# Zasilanie.net
KiCad netlist of a schematic drawn in Altium Designer
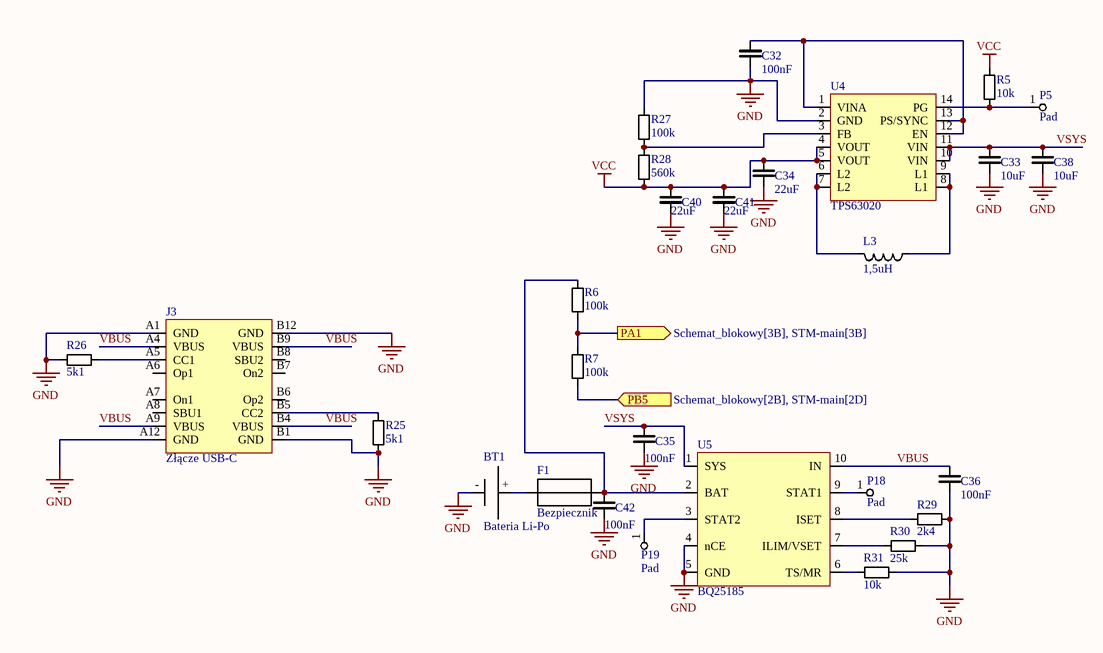
[diagram p0: Zasilanie.SchDoc]

(export (version "E")
  (design (tool "Eeschema 10.0.6"))
  (components
    (comp (ref "BT1")
      (value "Bateria Li-Po")
      (footprint "LP623255 3,7V 1100mAh")
      (fields (field (name "PARTNUMBER") "LP623255 3,7V 1100mAh"))
      (libsource (lib "Zasilanie") (part "Bateria Li-Po"))
    )
    (comp (ref "C32")
      (value "100nF")
      (footprint "0603_CAP")
      (description "Ceramic capacitor")
      (libsource (lib "Cap") (part "Cap"))
    )
    (comp (ref "C33")
      (value "10uF")
      (footprint "0603_CAP")
      (description "Ceramic capacitor")
      (libsource (lib "Cap") (part "Cap"))
    )
    (comp (ref "C34")
      (value "22uF")
      (footprint "0603_CAP")
      (description "Ceramic capacitor")
      (libsource (lib "Cap") (part "Cap"))
    )
    (comp (ref "C35")
      (value "100nF")
      (footprint "0603_CAP")
      (description "Ceramic capacitor")
      (libsource (lib "Cap") (part "Cap"))
    )
    (comp (ref "C36")
      (value "100nF")
      (footprint "0603_CAP")
      (description "Ceramic capacitor")
      (libsource (lib "Cap") (part "Cap"))
    )
    (comp (ref "C38")
      (value "10uF")
      (footprint "0603_CAP")
      (description "Ceramic capacitor")
      (libsource (lib "Cap") (part "Cap"))
    )
    (comp (ref "C40")
      (value "22uF")
      (footprint "0603_CAP")
      (description "Ceramic capacitor")
      (libsource (lib "Cap") (part "Cap"))
    )
    (comp (ref "C41")
      (value "22uF")
      (footprint "0603_CAP")
      (description "Ceramic capacitor")
      (libsource (lib "Cap") (part "Cap"))
    )
    (comp (ref "C42")
      (value "100nF")
      (footprint "0603_CAP")
      (description "Ceramic capacitor")
      (libsource (lib "Cap") (part "Cap"))
    )
    (comp (ref "F1")
      (value "Bezpiecznik")
      (footprint "0603_FUSE")
      (fields (field (name "PARTNUMBER") "FMC16132WBTP"))
      (libsource (lib "Zasilanie") (part "Bezpiecznik"))
    )
    (comp (ref "J3")
      (value "Złącze USB-C")
      (footprint "HRO_TYPE-C-31-M-12")
      (fields (field (name "PARTNUMBER") "1332645"))
      (libsource (lib "Zasilanie") (part "Zlacze USB-C"))
    )
    (comp (ref "L3")
      (value "1,5uH")
      (footprint "0603_IND")
      (description "Inductor")
      (fields (field (name "PARTNUMBER") "LSCNB1608HKT1R5MD"))
      (libsource (lib "Inductor") (part "Inductor"))
    )
    (comp (ref "P5") (value "Pad") (footprint "pad") (libsource (lib "PinLutowniczy") (part "Pad")))
    (comp (ref "P18") (value "Pad") (footprint "pad") (libsource (lib "PinLutowniczy") (part "Pad")))
    (comp (ref "P19") (value "Pad") (footprint "pad") (libsource (lib "PinLutowniczy") (part "Pad")))
    (comp (ref "R5")
      (value "10k")
      (footprint "0603_RES")
      (description "Resistor")
      (libsource (lib "RES") (part "RES"))
    )
    (comp (ref "R6")
      (value "100k")
      (footprint "0603_RES")
      (description "Resistor")
      (libsource (lib "RES") (part "RES"))
    )
    (comp (ref "R7")
      (value "100k")
      (footprint "0603_RES")
      (description "Resistor")
      (libsource (lib "RES") (part "RES"))
    )
    (comp (ref "R25")
      (value "5k1")
      (footprint "0603_RES")
      (description "Resistor")
      (libsource (lib "RES") (part "RES"))
    )
    (comp (ref "R26")
      (value "5k1")
      (footprint "0603_RES")
      (description "Resistor")
      (libsource (lib "RES") (part "RES"))
    )
    (comp (ref "R27")
      (value "100k")
      (footprint "0603_RES")
      (description "Resistor")
      (libsource (lib "RES") (part "RES"))
    )
    (comp (ref "R28")
      (value "560k")
      (footprint "0603_RES")
      (description "Resistor")
      (libsource (lib "RES") (part "RES"))
    )
    (comp (ref "R29")
      (value "2k4")
      (footprint "0603_RES")
      (description "Resistor")
      (libsource (lib "RES") (part "RES"))
    )
    (comp (ref "R30")
      (value "25k")
      (footprint "0603_RES")
      (description "Resistor")
      (libsource (lib "RES") (part "RES"))
    )
    (comp (ref "R31")
      (value "10k")
      (footprint "0603_RES")
      (description "Resistor")
      (libsource (lib "RES") (part "RES"))
    )
    (comp (ref "U4")
      (value "TPS63020")
      (footprint "IC_TPS63020DSJT")
      (description "Przetwornica impulsowa")
      (fields (field (name "PARTNUMBER") "TPS63020DSJR"))
      (libsource (lib "Zasilanie") (part "Stabilizator napięcia"))
    )
    (comp (ref "U5")
      (value "BQ25185")
      (footprint "SON50P250X250X80-11N")
      (description "Battery charger")
      (fields (field (name "PARTNUMBER") "BQ25185DLHR"))
      (libsource (lib "Zasilanie") (part "BQ25185"))
    )
  )
  (nets
    (net (code "1") (name "/PA1") (class "Default")
      (node (ref "R6") (pin "1") (pinfunction "1_1") (pintype "passive"))
      (node (ref "R7") (pin "2") (pinfunction "2_2") (pintype "passive"))
    )
    (net (code "2") (name "/PB5") (class "Default")
      (node (ref "R7") (pin "1") (pinfunction "1_1") (pintype "passive"))
    )
    (net (code "3") (name "/VBUS") (class "Default")
      (node (ref "C36") (pin "2") (pinfunction "2_2") (pintype "passive"))
      (node (ref "J3") (pin "A4") (pinfunction "VBUS_A4") (pintype "passive"))
      (node (ref "J3") (pin "A9") (pinfunction "VBUS_A9") (pintype "passive"))
      (node (ref "J3") (pin "B4") (pinfunction "VBUS_B4") (pintype "passive"))
      (node (ref "J3") (pin "B9") (pinfunction "VBUS_B9") (pintype "passive"))
      (node (ref "U5") (pin "10") (pinfunction "IN_10") (pintype "passive"))
    )
    (net (code "4") (name "/VSYS") (class "Default")
      (node (ref "C33") (pin "2") (pinfunction "2_2") (pintype "passive"))
      (node (ref "C35") (pin "2") (pinfunction "2_2") (pintype "passive"))
      (node (ref "C38") (pin "2") (pinfunction "2_2") (pintype "passive"))
      (node (ref "U4") (pin "10") (pinfunction "VIN_10") (pintype "passive"))
      (node (ref "U4") (pin "11") (pinfunction "VIN_11") (pintype "passive"))
      (node (ref "U5") (pin "1") (pinfunction "SYS_1") (pintype "passive"))
    )
    (net (code "5") (name "GND") (class "Default")
      (node (ref "BT1") (pin "-") (pintype "passive"))
      (node (ref "C32") (pin "1") (pinfunction "1_1") (pintype "passive"))
      (node (ref "C33") (pin "1") (pinfunction "1_1") (pintype "passive"))
      (node (ref "C34") (pin "1") (pinfunction "1_1") (pintype "passive"))
      (node (ref "C35") (pin "1") (pinfunction "1_1") (pintype "passive"))
      (node (ref "C36") (pin "1") (pinfunction "1_1") (pintype "passive"))
      (node (ref "C38") (pin "1") (pinfunction "1_1") (pintype "passive"))
      (node (ref "C40") (pin "1") (pinfunction "1_1") (pintype "passive"))
      (node (ref "C41") (pin "1") (pinfunction "1_1") (pintype "passive"))
      (node (ref "C42") (pin "1") (pinfunction "1_1") (pintype "passive"))
      (node (ref "J3") (pin "A1") (pinfunction "GND_A1") (pintype "passive"))
      (node (ref "J3") (pin "A12") (pinfunction "GND_A12") (pintype "passive"))
      (node (ref "J3") (pin "B1") (pinfunction "GND_B1") (pintype "passive"))
      (node (ref "J3") (pin "B12") (pinfunction "GND_B12") (pintype "passive"))
      (node (ref "R25") (pin "1") (pinfunction "1_1") (pintype "passive"))
      (node (ref "R26") (pin "2") (pinfunction "2_2") (pintype "passive"))
      (node (ref "R27") (pin "2") (pinfunction "2_2") (pintype "passive"))
      (node (ref "R29") (pin "2") (pinfunction "2_2") (pintype "passive"))
      (node (ref "R30") (pin "2") (pinfunction "2_2") (pintype "passive"))
      (node (ref "R31") (pin "1") (pinfunction "1_1") (pintype "passive"))
      (node (ref "U4") (pin "2") (pinfunction "GND_2") (pintype "passive"))
      (node (ref "U5") (pin "4") (pinfunction "nCE_4") (pintype "passive"))
      (node (ref "U5") (pin "5") (pinfunction "GND_5") (pintype "passive"))
    )
    (net (code "6") (name "Net-(BT1-Pad+)") (class "Default")
      (node (ref "BT1") (pin "+") (pintype "passive"))
      (node (ref "F1") (pin "1") (pintype "passive"))
    )
    (net (code "7") (name "Net-(J3-CC1)") (class "Default")
      (node (ref "J3") (pin "A5") (pinfunction "CC1_A5") (pintype "passive"))
      (node (ref "R26") (pin "1") (pinfunction "1_1") (pintype "passive"))
    )
    (net (code "8") (name "Net-(J3-CC2)") (class "Default")
      (node (ref "J3") (pin "B5") (pinfunction "CC2_B5") (pintype "passive"))
      (node (ref "R25") (pin "2") (pinfunction "2_2") (pintype "passive"))
    )
    (net (code "9") (name "Net-(L3-Pad1)") (class "Default")
      (node (ref "L3") (pin "1") (pinfunction "1_1") (pintype "passive"))
      (node (ref "U4") (pin "8") (pinfunction "L1_8") (pintype "passive"))
      (node (ref "U4") (pin "9") (pinfunction "L1_9") (pintype "passive"))
    )
    (net (code "10") (name "Net-(L3-Pad2)") (class "Default")
      (node (ref "L3") (pin "2") (pinfunction "2_2") (pintype "passive"))
      (node (ref "U4") (pin "6") (pinfunction "L2_6") (pintype "passive"))
      (node (ref "U4") (pin "7") (pinfunction "L2_7") (pintype "passive"))
    )
    (net (code "11") (name "Net-(U4-EN)") (class "Default")
      (node (ref "C32") (pin "2") (pinfunction "2_2") (pintype "passive"))
      (node (ref "U4") (pin "1") (pinfunction "VINA_1") (pintype "passive"))
      (node (ref "U4") (pin "12") (pinfunction "EN_12") (pintype "passive"))
      (node (ref "U4") (pin "13") (pinfunction "PS/SYNC_13") (pintype "passive"))
    )
    (net (code "12") (name "Net-(U4-FB)") (class "Default")
      (node (ref "R27") (pin "1") (pinfunction "1_1") (pintype "passive"))
      (node (ref "R28") (pin "2") (pinfunction "2_2") (pintype "passive"))
      (node (ref "U4") (pin "3") (pinfunction "FB_3") (pintype "passive"))
    )
    (net (code "13") (name "Net-(U4-PG)") (class "Default")
      (node (ref "P5") (pin "1") (pintype "passive"))
      (node (ref "R5") (pin "1") (pinfunction "1_1") (pintype "passive"))
      (node (ref "U4") (pin "14") (pinfunction "PG_14") (pintype "passive"))
    )
    (net (code "14") (name "Net-(U5-BAT)") (class "Default")
      (node (ref "C42") (pin "2") (pinfunction "2_2") (pintype "passive"))
      (node (ref "F1") (pin "2") (pintype "passive"))
      (node (ref "R6") (pin "2") (pinfunction "2_2") (pintype "passive"))
      (node (ref "U5") (pin "2") (pinfunction "BAT_2") (pintype "passive"))
    )
    (net (code "15") (name "Net-(U5-ILIM{slash}VSET)") (class "Default")
      (node (ref "R30") (pin "1") (pinfunction "1_1") (pintype "passive"))
      (node (ref "U5") (pin "7") (pinfunction "ILIM/VSET_7") (pintype "passive"))
    )
    (net (code "16") (name "Net-(U5-ISET)") (class "Default")
      (node (ref "R29") (pin "1") (pinfunction "1_1") (pintype "passive"))
      (node (ref "U5") (pin "8") (pinfunction "ISET_8") (pintype "passive"))
    )
    (net (code "17") (name "Net-(U5-STAT1)") (class "Default")
      (node (ref "P18") (pin "1") (pintype "passive"))
      (node (ref "U5") (pin "9") (pinfunction "STAT1_9") (pintype "passive"))
    )
    (net (code "18") (name "Net-(U5-STAT2)") (class "Default")
      (node (ref "P19") (pin "1") (pintype "passive"))
      (node (ref "U5") (pin "3") (pinfunction "STAT2_3") (pintype "passive"))
    )
    (net (code "19") (name "Net-(U5-TS{slash}MR)") (class "Default")
      (node (ref "R31") (pin "2") (pinfunction "2_2") (pintype "passive"))
      (node (ref "U5") (pin "6") (pinfunction "TS/MR_6") (pintype "passive"))
    )
    (net (code "20") (name "VCC") (class "Default")
      (node (ref "C34") (pin "2") (pinfunction "2_2") (pintype "passive"))
      (node (ref "C40") (pin "2") (pinfunction "2_2") (pintype "passive"))
      (node (ref "C41") (pin "2") (pinfunction "2_2") (pintype "passive"))
      (node (ref "R28") (pin "1") (pinfunction "1_1") (pintype "passive"))
      (node (ref "R5") (pin "2") (pinfunction "2_2") (pintype "passive"))
      (node (ref "U4") (pin "4") (pinfunction "VOUT_4") (pintype "passive"))
      (node (ref "U4") (pin "5") (pinfunction "VOUT_5") (pintype "passive"))
    )
    (net (code "21") (name "unconnected-(J3-On1-PadA7)") (class "Default")
      (node (ref "J3") (pin "A7") (pinfunction "On1_A7") (pintype "passive"))
    )
    (net (code "22") (name "unconnected-(J3-On2-PadB7)") (class "Default")
      (node (ref "J3") (pin "B7") (pinfunction "On2_B7") (pintype "passive"))
    )
    (net (code "23") (name "unconnected-(J3-Op1-PadA6)") (class "Default")
      (node (ref "J3") (pin "A6") (pinfunction "Op1_A6") (pintype "passive"))
    )
    (net (code "24") (name "unconnected-(J3-Op2-PadB6)") (class "Default")
      (node (ref "J3") (pin "B6") (pinfunction "Op2_B6") (pintype "passive"))
    )
    (net (code "25") (name "unconnected-(J3-SBU1-PadA8)") (class "Default")
      (node (ref "J3") (pin "A8") (pinfunction "SBU1_A8") (pintype "passive"))
    )
    (net (code "26") (name "unconnected-(J3-SBU2-PadB8)") (class "Default")
      (node (ref "J3") (pin "B8") (pinfunction "SBU2_B8") (pintype "passive"))
    )
  )
)
